# iot.net
KiCad netlist of a schematic drawn in EAGLE
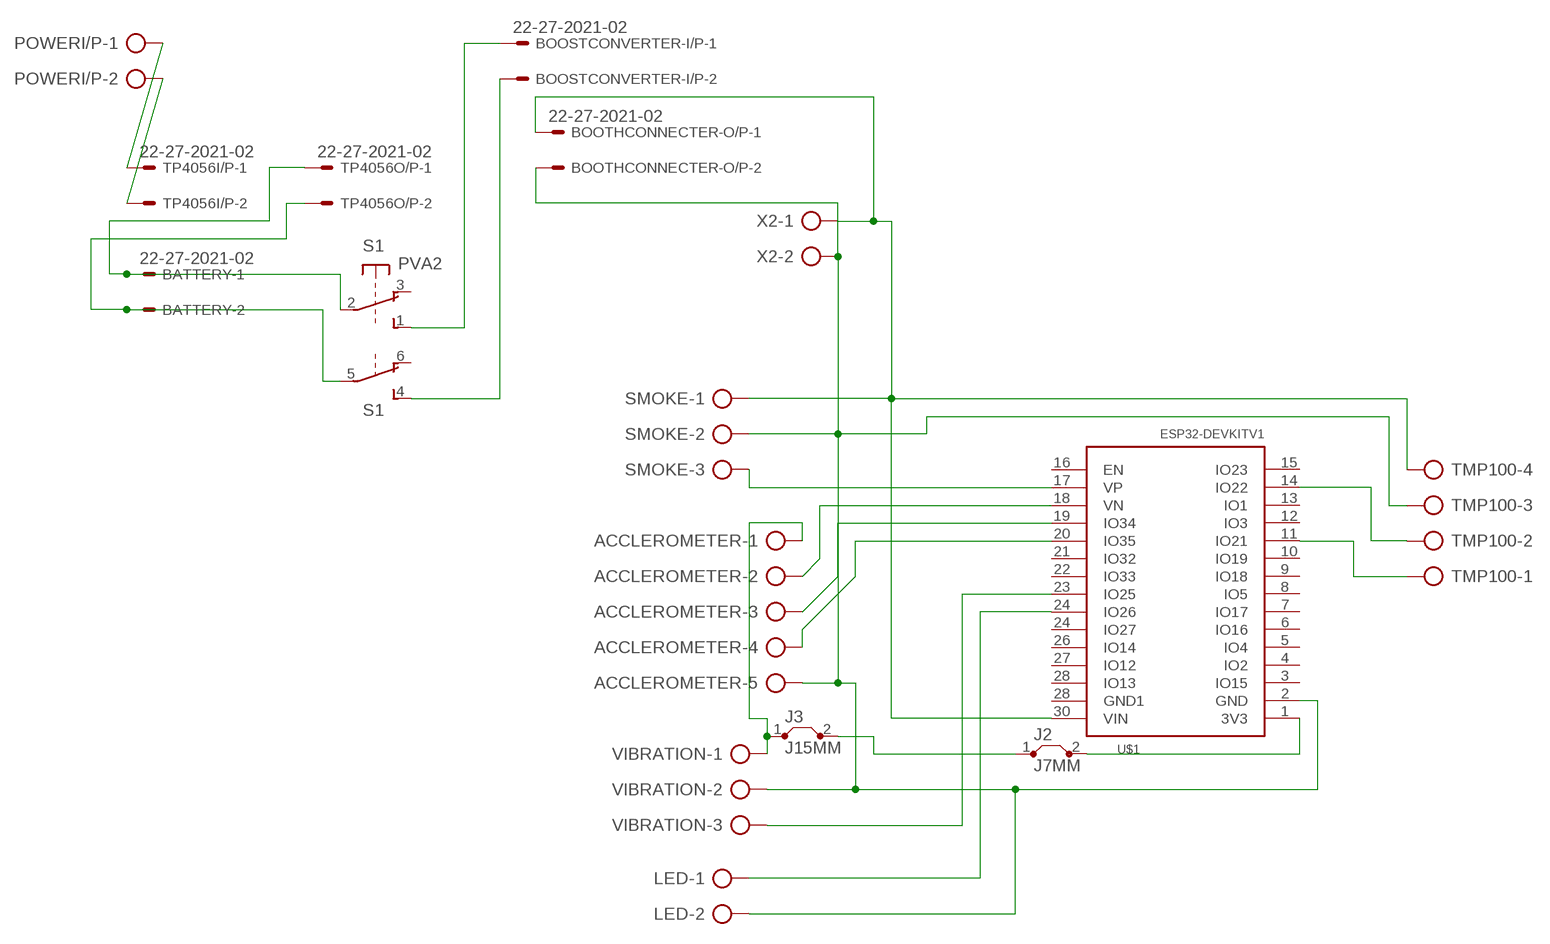
[diagram p0: schematic, sheet 1]

(export (version "E")
  (design (tool "Eeschema 10.0.6"))
  (components
    (comp (ref "ACCLEROMETER")
      (value "AK500/5-H")
      (footprint "eagle-import:AK500_5-H")
      (libsource (lib "eagle-import") (part "AK500/5-H"))
    )
    (comp (ref "BATTERY")
      (value "22-27-2021-02")
      (footprint "eagle-import:6410-02")
      (fields (field (name "MF") "MOLEX"))
      (libsource (lib "eagle-import") (part "22-?-0227-2021"))
    )
    (comp (ref "BOOSTCONVERTER-I/P")
      (value "22-27-2021-02")
      (footprint "eagle-import:6410-02")
      (fields (field (name "MF") "MOLEX"))
      (libsource (lib "eagle-import") (part "22-?-0227-2021"))
    )
    (comp (ref "BOOTHCONNECTER-O/P")
      (value "22-27-2021-02")
      (footprint "eagle-import:6410-02")
      (fields (field (name "MF") "MOLEX"))
      (libsource (lib "eagle-import") (part "22-?-0227-2021"))
    )
    (comp (ref "J2")
      (value "J7MM")
      (footprint "eagle-import:07")
      (libsource (lib "eagle-import") (part "J7MM"))
    )
    (comp (ref "J3")
      (value "J15MM")
      (footprint "eagle-import:15")
      (libsource (lib "eagle-import") (part "J15MM"))
    )
    (comp (ref "LED")
      (value "AK500/2-H")
      (footprint "eagle-import:AK500_2-H")
      (libsource (lib "eagle-import") (part "AK500/2-H"))
    )
    (comp (ref "POWERI/P")
      (value "AK500/2-H")
      (footprint "eagle-import:AK500_2-H")
      (libsource (lib "eagle-import") (part "AK500/2-H"))
    )
    (comp (ref "S1")
      (value "PVA2")
      (footprint "eagle-import:PVA2F")
      (libsource (lib "eagle-import") (part "PVA2"))
    )
    (comp (ref "SMOKE")
      (value "AK500/3-H")
      (footprint "eagle-import:AK500_3-H")
      (libsource (lib "eagle-import") (part "AK500/3-H"))
    )
    (comp (ref "TMP100")
      (value "AK500/4-H")
      (footprint "eagle-import:AK500_4-H")
      (libsource (lib "eagle-import") (part "AK500/4-H"))
    )
    (comp (ref "TP4056I/P")
      (value "22-27-2021-02")
      (footprint "eagle-import:6410-02")
      (fields (field (name "MF") "MOLEX"))
      (libsource (lib "eagle-import") (part "22-?-0227-2021"))
    )
    (comp (ref "TP4056O/P")
      (value "22-27-2021-02")
      (footprint "eagle-import:6410-02")
      (fields (field (name "MF") "MOLEX"))
      (libsource (lib "eagle-import") (part "22-?-0227-2021"))
    )
    (comp (ref "U$1")
      (value "ESP32DEVKITV1")
      (footprint "eagle-import:ESP32-DEVKITV1")
      (libsource (lib "eagle-import") (part "ESP32DEVKITV1"))
    )
    (comp (ref "VIBRATION")
      (value "AK500/3-H")
      (footprint "eagle-import:AK500_3-H")
      (libsource (lib "eagle-import") (part "AK500/3-H"))
    )
    (comp (ref "X2")
      (value "AK500/2-H")
      (footprint "eagle-import:AK500_2-H")
      (libsource (lib "eagle-import") (part "AK500/2-H"))
    )
  )
  (nets
    (net (code "1") (name "Net-(ACCLEROMETERA-KL)") (class "Default")
      (node (ref "ACCLEROMETER") (pin "1") (pinfunction "KL_1") (pintype "passive"))
      (node (ref "J3") (pin "1") (pinfunction "1_1") (pintype "passive"))
      (node (ref "VIBRATION") (pin "1") (pinfunction "KL_1") (pintype "passive"))
    )
    (net (code "2") (name "Net-(ACCLEROMETERB-KL)") (class "Default")
      (node (ref "ACCLEROMETER") (pin "2") (pinfunction "KL_2") (pintype "passive"))
      (node (ref "U$1") (pin "18") (pinfunction "VN_18") (pintype "bidirectional"))
    )
    (net (code "3") (name "Net-(ACCLEROMETERC-KL)") (class "Default")
      (node (ref "ACCLEROMETER") (pin "3") (pinfunction "KL_3") (pintype "passive"))
      (node (ref "U$1") (pin "19") (pinfunction "IO34_19") (pintype "bidirectional"))
    )
    (net (code "4") (name "Net-(ACCLEROMETERD-KL)") (class "Default")
      (node (ref "ACCLEROMETER") (pin "4") (pinfunction "KL_4") (pintype "passive"))
      (node (ref "U$1") (pin "20") (pinfunction "IO35_20") (pintype "bidirectional"))
    )
    (net (code "5") (name "Net-(ACCLEROMETERE-KL)") (class "Default")
      (node (ref "ACCLEROMETER") (pin "5") (pinfunction "KL_5") (pintype "passive"))
      (node (ref "BOOTHCONNECTER-O/P") (pin "2") (pinfunction "S_2") (pintype "passive"))
      (node (ref "LED") (pin "2") (pinfunction "KL_2") (pintype "passive"))
      (node (ref "SMOKE") (pin "2") (pinfunction "KL_2") (pintype "passive"))
      (node (ref "TMP100") (pin "3") (pinfunction "KL_3") (pintype "passive"))
      (node (ref "U$1") (pin "2") (pinfunction "GND_2") (pintype "bidirectional"))
      (node (ref "VIBRATION") (pin "2") (pinfunction "KL_2") (pintype "passive"))
      (node (ref "X2") (pin "2") (pinfunction "KL_2") (pintype "passive"))
    )
    (net (code "6") (name "Net-(BATTERYA-S)") (class "Default")
      (node (ref "BATTERY") (pin "1") (pinfunction "S_1") (pintype "passive"))
      (node (ref "S1") (pin "2") (pinfunction "P_2") (pintype "passive"))
      (node (ref "TP4056O/P") (pin "1") (pinfunction "S_1") (pintype "passive"))
    )
    (net (code "7") (name "Net-(BATTERYB-S)") (class "Default")
      (node (ref "BATTERY") (pin "2") (pinfunction "S_2") (pintype "passive"))
      (node (ref "S1") (pin "5") (pinfunction "P_5") (pintype "passive"))
      (node (ref "TP4056O/P") (pin "2") (pinfunction "S_2") (pintype "passive"))
    )
    (net (code "8") (name "Net-(BOOSTCONVERTER-I/PA-S)") (class "Default")
      (node (ref "BOOSTCONVERTER-I/P") (pin "1") (pinfunction "S_1") (pintype "passive"))
      (node (ref "S1") (pin "1") (pinfunction "S_1") (pintype "passive"))
    )
    (net (code "9") (name "Net-(BOOSTCONVERTER-I/PB-S)") (class "Default")
      (node (ref "BOOSTCONVERTER-I/P") (pin "2") (pinfunction "S_2") (pintype "passive"))
      (node (ref "S1") (pin "4") (pinfunction "S_4") (pintype "passive"))
    )
    (net (code "10") (name "Net-(BOOTHCONNECTER-O/PA-S)") (class "Default")
      (node (ref "BOOTHCONNECTER-O/P") (pin "1") (pinfunction "S_1") (pintype "passive"))
      (node (ref "SMOKE") (pin "1") (pinfunction "KL_1") (pintype "passive"))
      (node (ref "TMP100") (pin "4") (pinfunction "KL_4") (pintype "passive"))
      (node (ref "U$1") (pin "30") (pinfunction "VIN_30") (pintype "bidirectional"))
      (node (ref "X2") (pin "1") (pinfunction "KL_1") (pintype "passive"))
    )
    (net (code "11") (name "Net-(J2-Pad1)") (class "Default")
      (node (ref "J2") (pin "1") (pinfunction "1_1") (pintype "passive"))
      (node (ref "J3") (pin "2") (pinfunction "2_2") (pintype "passive"))
    )
    (net (code "12") (name "Net-(LEDA-KL)") (class "Default")
      (node (ref "LED") (pin "1") (pinfunction "KL_1") (pintype "passive"))
      (node (ref "U$1") (pin "24") (pinfunction "IO26_24") (pintype "bidirectional"))
    )
    (net (code "13") (name "Net-(POWERI/PA-KL)") (class "Default")
      (node (ref "POWERI/P") (pin "1") (pinfunction "KL_1") (pintype "passive"))
      (node (ref "TP4056I/P") (pin "1") (pinfunction "S_1") (pintype "passive"))
    )
    (net (code "14") (name "Net-(POWERI/PB-KL)") (class "Default")
      (node (ref "POWERI/P") (pin "2") (pinfunction "KL_2") (pintype "passive"))
      (node (ref "TP4056I/P") (pin "2") (pinfunction "S_2") (pintype "passive"))
    )
    (net (code "15") (name "Net-(SMOKEC-KL)") (class "Default")
      (node (ref "SMOKE") (pin "3") (pinfunction "KL_3") (pintype "passive"))
      (node (ref "U$1") (pin "17") (pinfunction "VP_17") (pintype "bidirectional"))
    )
    (net (code "16") (name "Net-(TMP100A-KL)") (class "Default")
      (node (ref "TMP100") (pin "1") (pinfunction "KL_1") (pintype "passive"))
      (node (ref "U$1") (pin "11") (pinfunction "IO21_11") (pintype "bidirectional"))
    )
    (net (code "17") (name "Net-(TMP100B-KL)") (class "Default")
      (node (ref "TMP100") (pin "2") (pinfunction "KL_2") (pintype "passive"))
      (node (ref "U$1") (pin "14") (pinfunction "IO22_14") (pintype "bidirectional"))
    )
    (net (code "18") (name "Net-(U$1-3V3)") (class "Default")
      (node (ref "J2") (pin "2") (pinfunction "2_2") (pintype "passive"))
      (node (ref "U$1") (pin "1") (pinfunction "3V3_1") (pintype "bidirectional"))
    )
    (net (code "19") (name "Net-(U$1-IO25)") (class "Default")
      (node (ref "U$1") (pin "23") (pinfunction "IO25_23") (pintype "bidirectional"))
      (node (ref "VIBRATION") (pin "3") (pinfunction "KL_3") (pintype "passive"))
    )
    (net (code "20") (name "unconnected-(S1A-O-Pad3)") (class "Default")
      (node (ref "S1") (pin "3") (pinfunction "O_3") (pintype "passive"))
    )
    (net (code "21") (name "unconnected-(S1B-O-Pad6)") (class "Default")
      (node (ref "S1") (pin "6") (pinfunction "O_6") (pintype "passive"))
    )
    (net (code "22") (name "unconnected-(U$1-EN-Pad16)") (class "Default")
      (node (ref "U$1") (pin "16") (pinfunction "EN_16") (pintype "bidirectional"))
    )
    (net (code "23") (name "unconnected-(U$1-GND1-Pad28)") (class "Default")
      (node (ref "U$1") (pin "28") (pinfunction "GND1_28") (pintype "bidirectional"))
    )
    (net (code "24") (name "unconnected-(U$1-IO1-Pad13)") (class "Default")
      (node (ref "U$1") (pin "13") (pinfunction "IO1_13") (pintype "bidirectional"))
    )
    (net (code "25") (name "unconnected-(U$1-IO2-Pad4)") (class "Default")
      (node (ref "U$1") (pin "4") (pinfunction "IO2_4") (pintype "bidirectional"))
    )
    (net (code "26") (name "unconnected-(U$1-IO3-Pad12)") (class "Default")
      (node (ref "U$1") (pin "12") (pinfunction "IO3_12") (pintype "bidirectional"))
    )
    (net (code "27") (name "unconnected-(U$1-IO4-Pad5)") (class "Default")
      (node (ref "U$1") (pin "5") (pinfunction "IO4_5") (pintype "bidirectional"))
    )
    (net (code "28") (name "unconnected-(U$1-IO5-Pad8)") (class "Default")
      (node (ref "U$1") (pin "8") (pinfunction "IO5_8") (pintype "bidirectional"))
    )
    (net (code "29") (name "unconnected-(U$1-IO12-Pad27)") (class "Default")
      (node (ref "U$1") (pin "27") (pinfunction "IO12_27") (pintype "bidirectional"))
    )
    (net (code "30") (name "unconnected-(U$1-IO13-Pad28)") (class "Default")
      (node (ref "U$1") (pin "28") (pinfunction "IO13_28") (pintype "bidirectional"))
    )
    (net (code "31") (name "unconnected-(U$1-IO14-Pad26)") (class "Default")
      (node (ref "U$1") (pin "26") (pinfunction "IO14_26") (pintype "bidirectional"))
    )
    (net (code "32") (name "unconnected-(U$1-IO15-Pad3)") (class "Default")
      (node (ref "U$1") (pin "3") (pinfunction "IO15_3") (pintype "bidirectional"))
    )
    (net (code "33") (name "unconnected-(U$1-IO16-Pad6)") (class "Default")
      (node (ref "U$1") (pin "6") (pinfunction "IO16_6") (pintype "bidirectional"))
    )
    (net (code "34") (name "unconnected-(U$1-IO17-Pad7)") (class "Default")
      (node (ref "U$1") (pin "7") (pinfunction "IO17_7") (pintype "bidirectional"))
    )
    (net (code "35") (name "unconnected-(U$1-IO18-Pad9)") (class "Default")
      (node (ref "U$1") (pin "9") (pinfunction "IO18_9") (pintype "bidirectional"))
    )
    (net (code "36") (name "unconnected-(U$1-IO19-Pad10)") (class "Default")
      (node (ref "U$1") (pin "10") (pinfunction "IO19_10") (pintype "bidirectional"))
    )
    (net (code "37") (name "unconnected-(U$1-IO23-Pad15)") (class "Default")
      (node (ref "U$1") (pin "15") (pinfunction "IO23_15") (pintype "bidirectional"))
    )
    (net (code "38") (name "unconnected-(U$1-IO27-Pad24)") (class "Default")
      (node (ref "U$1") (pin "24") (pinfunction "IO27_24") (pintype "bidirectional"))
    )
    (net (code "39") (name "unconnected-(U$1-IO32-Pad21)") (class "Default")
      (node (ref "U$1") (pin "21") (pinfunction "IO32_21") (pintype "bidirectional"))
    )
    (net (code "40") (name "unconnected-(U$1-IO33-Pad22)") (class "Default")
      (node (ref "U$1") (pin "22") (pinfunction "IO33_22") (pintype "bidirectional"))
    )
  )
)
